# Peripherals.net
KiCad netlist of a schematic drawn in Altium Designer
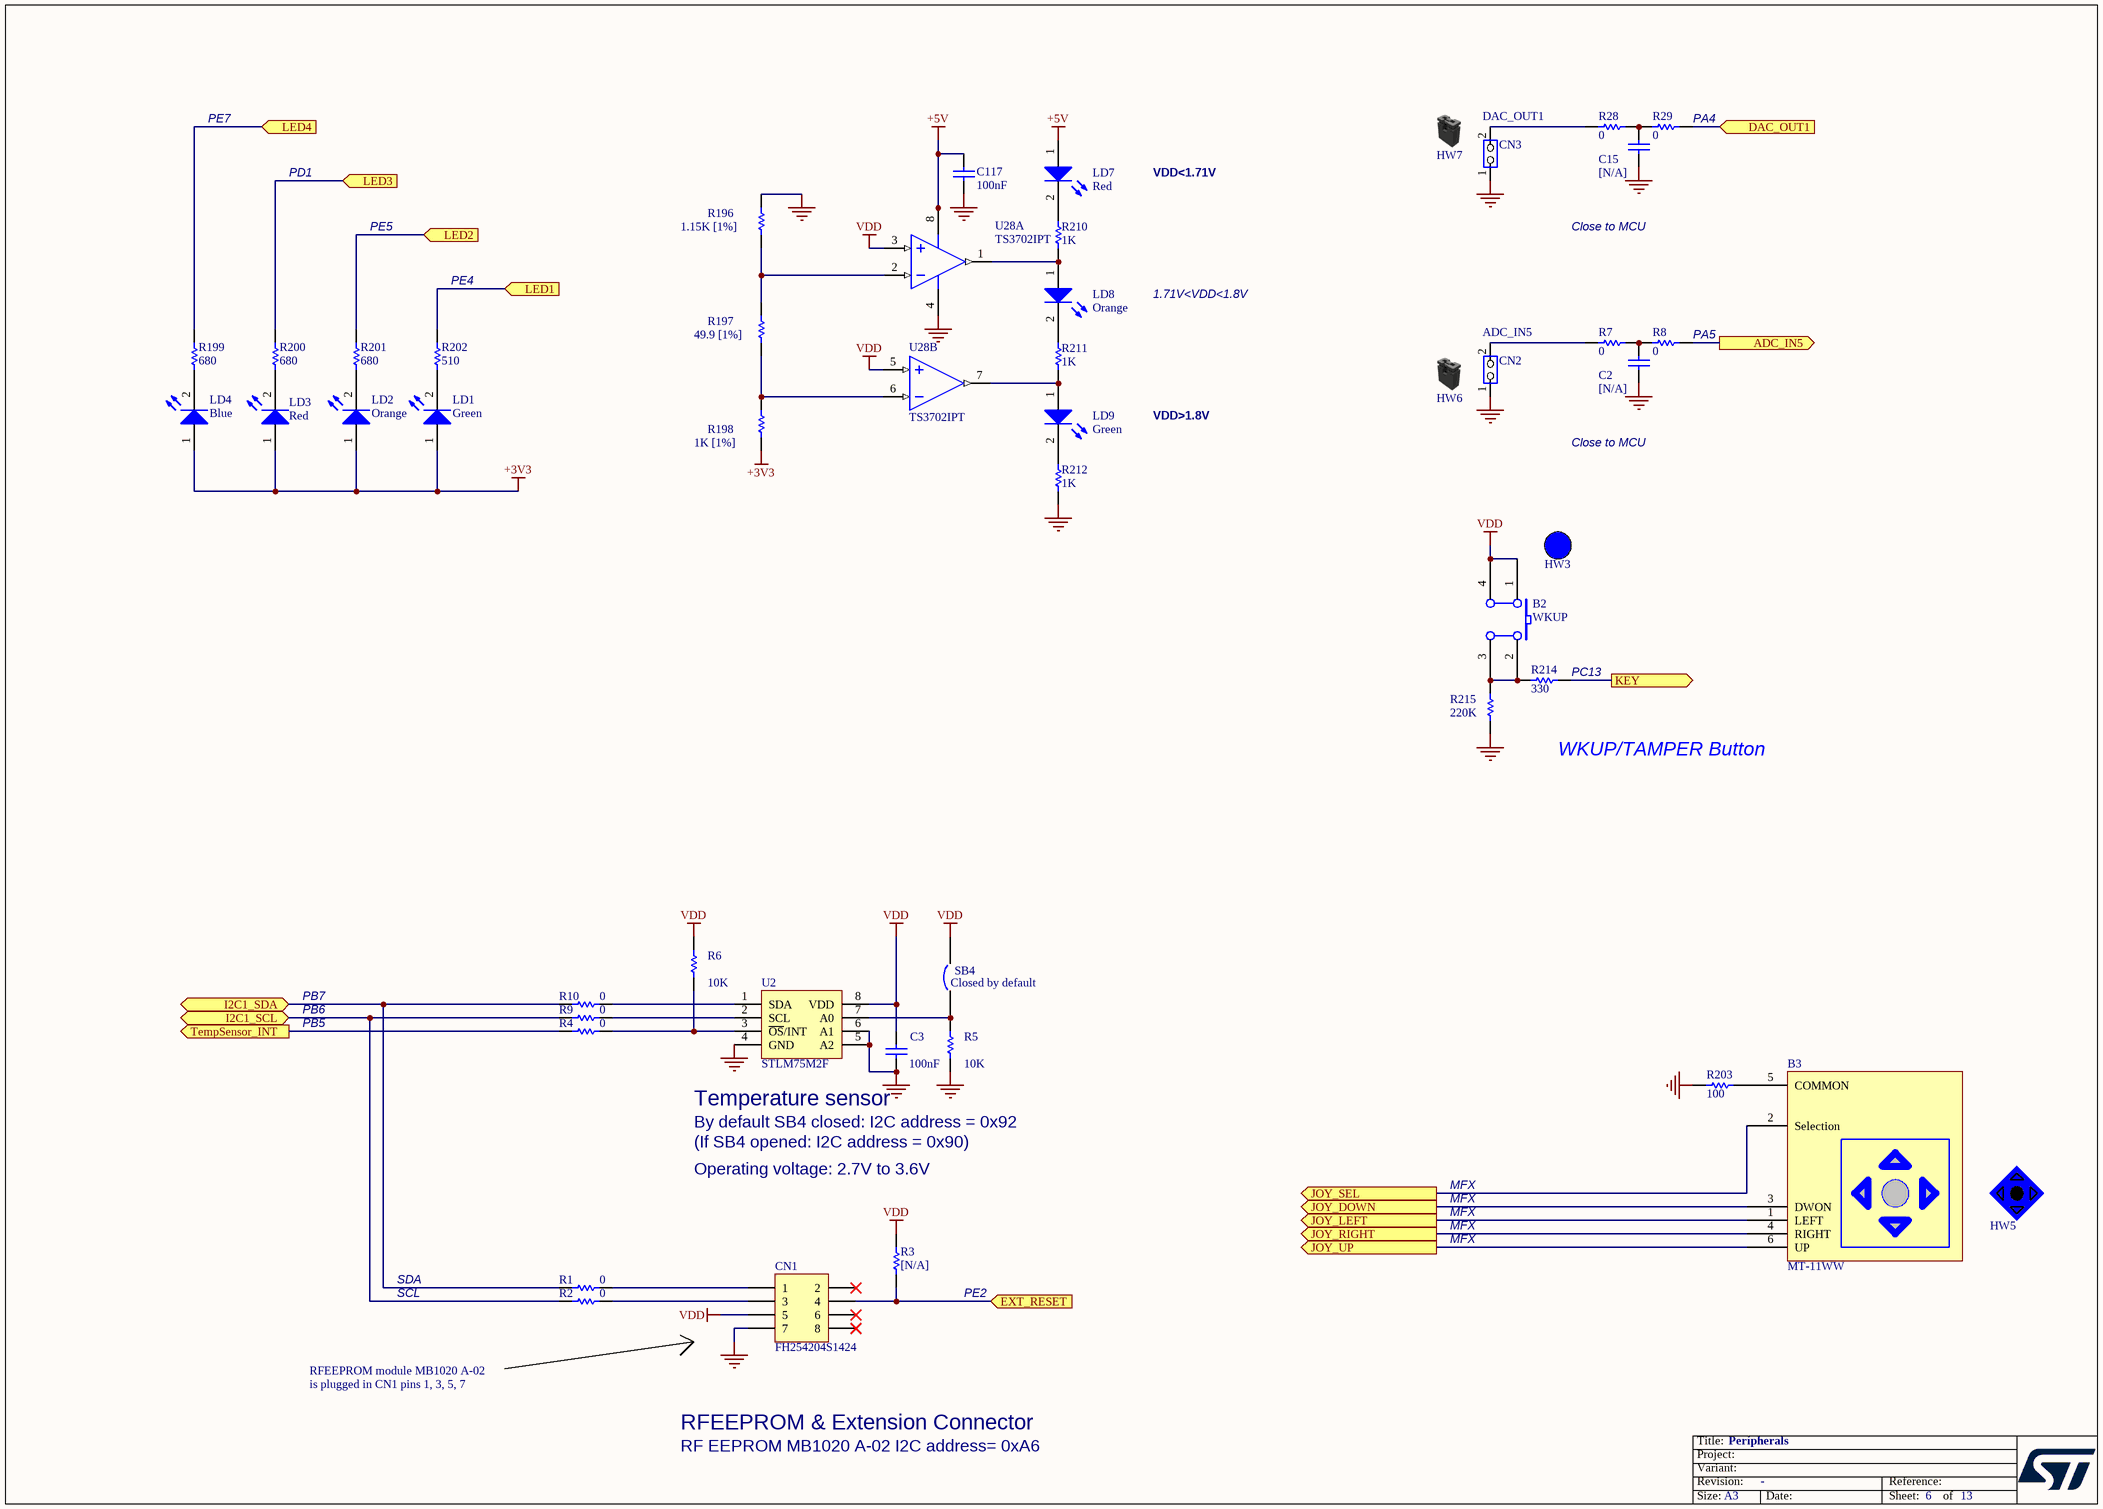
[diagram p0: Peripherals.SchDoc]

(export (version "E")
  (design (tool "Eeschema 10.0.6"))
  (components
    (comp (ref "B2")
      (value "WKUP")
      (footprint "PB10")
      (description "SE PUSHBUTTON")
      (libsource (lib "Documents") (part "SW PUSHBUTTON"))
    )
    (comp (ref "B3")
      (value "MT-11WW")
      (footprint "MT-008A")
      (description "Joystick")
      (libsource (lib "MB513") (part "MT-008A"))
    )
    (comp (ref "C2")
      (value "[N/A]")
      (footprint "0603C")
      (description "Capacitor")
      (fields (field (name "PUBLISHER") "Altium Limited"))
      (libsource (lib "Miscellaneous Devices") (part "cap"))
    )
    (comp (ref "C3")
      (value "100nF")
      (footprint "0402C")
      (description "Capacitor")
      (fields (field (name "PUBLISHER") "Altium Limited"))
      (libsource (lib "Miscellaneous Devices") (part "cap"))
    )
    (comp (ref "C15")
      (value "[N/A]")
      (footprint "0603C")
      (description "Capacitor")
      (fields (field (name "PUBLISHER") "Altium Limited"))
      (libsource (lib "Miscellaneous Devices") (part "cap"))
    )
    (comp (ref "C117")
      (value "100nF")
      (footprint "0402C")
      (description "Capacitor")
      (fields (field (name "PUBLISHER") "Altium Limited"))
      (libsource (lib "Miscellaneous Devices") (part "CAP"))
    )
    (comp (ref "CN1")
      (value "FH254204S1424")
      (footprint "SSM-104-L-DH")
      (description "Header, 5-Pin, Dual row")
      (fields (field (name "PUBLISHER") "Altium Limited"))
      (libsource (lib "mb1045") (part "SSM-104-L-DH"))
    )
    (comp (ref "CN2")
      (value "Header 2X1")
      (footprint "SIP2")
      (fields (field (name "SILKSCREEN") "ADC_IN5"))
      (libsource (lib "*") (part "JP2"))
    )
    (comp (ref "CN3")
      (value "Header 2X1")
      (footprint "SIP2")
      (fields (field (name "SILKSCREEN") "DAC_OUT1"))
      (libsource (lib "*") (part "JP2"))
    )
    (comp (ref "HW3") (value "BUTTON_HAT_BLUE") (libsource (lib "MB1168") (part "BUTTON_HAT_BLUE")))
    (comp (ref "HW5") (value "JOYSTICK_BLUE_HAT") (libsource (lib "MB1168") (part "JOYSTICK_BLUE_HAT")))
    (comp (ref "HW6") (value "Shunt Black 2.54mm") (libsource (lib "MB1168") (part "Shunt Black 2.54mm")))
    (comp (ref "HW7") (value "Shunt Black 2.54mm") (libsource (lib "MB1168") (part "Shunt Black 2.54mm")))
    (comp (ref "LD1")
      (value "Green")
      (footprint "0603D")
      (description "Typical RED, GREEN, YELLOW, AMBER GaAs LED")
      (fields (field (name "PUBLISHER") "Altium Limited"))
      (libsource (lib "Miscellaneous Devices") (part "LED2"))
    )
    (comp (ref "LD2")
      (value "Orange")
      (footprint "0603D")
      (description "Typical RED, GREEN, YELLOW, AMBER GaAs LED")
      (fields (field (name "PUBLISHER") "Altium Limited"))
      (libsource (lib "Miscellaneous Devices") (part "LED2"))
    )
    (comp (ref "LD3")
      (value "Red")
      (footprint "0603D")
      (description "Typical RED, GREEN, YELLOW, AMBER GaAs LED")
      (fields (field (name "PUBLISHER") "Altium Limited"))
      (libsource (lib "Miscellaneous Devices") (part "LED2"))
    )
    (comp (ref "LD4")
      (value "Blue")
      (footprint "0603D")
      (description "Typical RED, GREEN, YELLOW, AMBER GaAs LED")
      (fields (field (name "PUBLISHER") "Altium Limited"))
      (libsource (lib "Miscellaneous Devices") (part "LED2"))
    )
    (comp (ref "LD7")
      (value "Red")
      (footprint "0603D")
      (description "Typical RED, GREEN, YELLOW, AMBER GaAs LED")
      (fields (field (name "PUBLISHER") "Altium Limited"))
      (libsource (lib "Miscellaneous Devices") (part "LED2"))
    )
    (comp (ref "LD8")
      (value "Orange")
      (footprint "0603D")
      (description "Typical RED, GREEN, YELLOW, AMBER GaAs LED")
      (fields (field (name "PUBLISHER") "Altium Limited"))
      (libsource (lib "Miscellaneous Devices") (part "LED2"))
    )
    (comp (ref "LD9")
      (value "Green")
      (footprint "0603D")
      (description "Typical RED, GREEN, YELLOW, AMBER GaAs LED")
      (fields (field (name "PUBLISHER") "Altium Limited"))
      (libsource (lib "Miscellaneous Devices") (part "LED2"))
    )
    (comp (ref "R1")
      (value "0")
      (footprint "0603R")
      (description "Resistor")
      (fields (field (name "PUBLISHER") "Altium Limited"))
      (libsource (lib "Miscellaneous Devices") (part "Res1"))
    )
    (comp (ref "R2")
      (value "0")
      (footprint "0603R")
      (description "Resistor")
      (fields (field (name "PUBLISHER") "Altium Limited"))
      (libsource (lib "Miscellaneous Devices") (part "Res1"))
    )
    (comp (ref "R3")
      (value "[N/A]")
      (footprint "0603R")
      (description "Resistor")
      (fields (field (name "PUBLISHER") "Altium Limited"))
      (libsource (lib "Miscellaneous Devices") (part "Res1"))
    )
    (comp (ref "R4")
      (value "0")
      (footprint "0603R")
      (description "Resistor")
      (fields (field (name "PUBLISHER") "Altium Limited"))
      (libsource (lib "Miscellaneous Devices") (part "Res1"))
    )
    (comp (ref "R5")
      (value "10K")
      (footprint "0402R")
      (description "Resistor")
      (fields (field (name "PUBLISHER") "Altium Limited"))
      (libsource (lib "Miscellaneous Devices") (part "res1"))
    )
    (comp (ref "R6")
      (value "10K")
      (footprint "0402R")
      (description "Resistor")
      (fields (field (name "PUBLISHER") "Altium Limited"))
      (libsource (lib "Miscellaneous Devices") (part "res1"))
    )
    (comp (ref "R7")
      (value "0")
      (footprint "0603R")
      (description "Resistor")
      (fields (field (name "PUBLISHER") "Altium Limited"))
      (libsource (lib "Miscellaneous Devices") (part "Res1"))
    )
    (comp (ref "R8")
      (value "0")
      (footprint "0603R")
      (description "Resistor")
      (fields (field (name "PUBLISHER") "Altium Limited"))
      (libsource (lib "Miscellaneous Devices") (part "Res1"))
    )
    (comp (ref "R9")
      (value "0")
      (footprint "0603R")
      (description "Resistor")
      (fields (field (name "PUBLISHER") "Altium Limited"))
      (libsource (lib "Miscellaneous Devices") (part "Res1"))
    )
    (comp (ref "R10")
      (value "0")
      (footprint "0603R")
      (description "Resistor")
      (fields (field (name "PUBLISHER") "Altium Limited"))
      (libsource (lib "Miscellaneous Devices") (part "Res1"))
    )
    (comp (ref "R28")
      (value "0")
      (footprint "0603R")
      (description "Resistor")
      (fields (field (name "PUBLISHER") "Altium Limited"))
      (libsource (lib "Miscellaneous Devices") (part "Res1"))
    )
    (comp (ref "R29")
      (value "0")
      (footprint "0603R")
      (description "Resistor")
      (fields (field (name "PUBLISHER") "Altium Limited"))
      (libsource (lib "Miscellaneous Devices") (part "Res1"))
    )
    (comp (ref "R196")
      (value "1.15K [1%]")
      (footprint "0603R")
      (description "Resistor")
      (fields (field (name "PUBLISHER") "Altium Limited"))
      (libsource (lib "Miscellaneous Devices") (part "Res1"))
    )
    (comp (ref "R197")
      (value "49.9 [1%]")
      (footprint "0603R")
      (description "Resistor")
      (fields (field (name "PUBLISHER") "Altium Limited"))
      (libsource (lib "Miscellaneous Devices") (part "Res1"))
    )
    (comp (ref "R198")
      (value "1K [1%]")
      (footprint "0603R")
      (description "Resistor")
      (fields (field (name "PUBLISHER") "Altium Limited"))
      (libsource (lib "Miscellaneous Devices") (part "Res1"))
    )
    (comp (ref "R199")
      (value "680")
      (footprint "0402R")
      (description "Resistor")
      (fields (field (name "PUBLISHER") "Altium Limited"))
      (libsource (lib "Miscellaneous Devices") (part "Res1"))
    )
    (comp (ref "R200")
      (value "680")
      (footprint "0402R")
      (description "Resistor")
      (fields (field (name "PUBLISHER") "Altium Limited"))
      (libsource (lib "Miscellaneous Devices") (part "Res1"))
    )
    (comp (ref "R201")
      (value "680")
      (footprint "0402R")
      (description "Resistor")
      (fields (field (name "PUBLISHER") "Altium Limited"))
      (libsource (lib "Miscellaneous Devices") (part "Res1"))
    )
    (comp (ref "R202")
      (value "510")
      (footprint "0402R")
      (description "Resistor")
      (fields (field (name "PUBLISHER") "Altium Limited"))
      (libsource (lib "Miscellaneous Devices") (part "Res1"))
    )
    (comp (ref "R203")
      (value "100")
      (footprint "0402R")
      (description "Resistor")
      (fields (field (name "PUBLISHER") "Altium Limited"))
      (libsource (lib "Miscellaneous Devices") (part "Res1"))
    )
    (comp (ref "R210")
      (value "1K")
      (footprint "0402R")
      (description "Resistor")
      (fields (field (name "PUBLISHER") "Altium Limited"))
      (libsource (lib "Miscellaneous Devices") (part "Res1"))
    )
    (comp (ref "R211")
      (value "1K")
      (footprint "0402R")
      (description "Resistor")
      (fields (field (name "PUBLISHER") "Altium Limited"))
      (libsource (lib "Miscellaneous Devices") (part "Res1"))
    )
    (comp (ref "R212")
      (value "1K")
      (footprint "0402R")
      (description "Resistor")
      (fields (field (name "PUBLISHER") "Altium Limited"))
      (libsource (lib "Miscellaneous Devices") (part "Res1"))
    )
    (comp (ref "R214")
      (value "330")
      (footprint "0603R")
      (description "Resistor")
      (fields (field (name "PUBLISHER") "Altium Limited"))
      (libsource (lib "Miscellaneous Devices") (part "Res1"))
    )
    (comp (ref "R215")
      (value "220K")
      (footprint "0402R")
      (description "Resistor")
      (fields (field (name "PUBLISHER") "Altium Limited"))
      (libsource (lib "Miscellaneous Devices") (part "res1"))
    )
    (comp (ref "SB4")
      (value "Closed by default")
      (footprint "SB_0603")
      (description "Circuit Breaker")
      (fields (field (name "PUBLISHER") "Altium Limited"))
      (libsource (lib "Miscellaneous Devices") (part "Circuit Breaker"))
    )
    (comp (ref "U2")
      (value "STLM75M2F")
      (footprint "SOIC8_1R27_4R9X6")
      (libsource (lib "MB525") (part "STLM75DW2F"))
    )
    (comp (ref "U28")
      (value "TS3702IPT")
      (footprint "TSSOP8_0R65_3X6R4")
      (libsource (lib "MB819") (part "LM393PT"))
    )
  )
  (nets
    (net (code "1") (name "+3V3") (class "Default")
      (node (ref "LD1") (pin "1") (pinfunction "A_1") (pintype "passive"))
      (node (ref "LD2") (pin "1") (pinfunction "A_1") (pintype "passive"))
      (node (ref "LD3") (pin "1") (pinfunction "A_1") (pintype "passive"))
      (node (ref "LD4") (pin "1") (pinfunction "A_1") (pintype "passive"))
      (node (ref "R198") (pin "1") (pinfunction "1_1") (pintype "passive"))
    )
    (net (code "2") (name "+5V") (class "Default")
      (node (ref "C117") (pin "2") (pinfunction "2_2") (pintype "passive"))
      (node (ref "LD7") (pin "1") (pinfunction "A_1") (pintype "passive"))
      (node (ref "U28") (pin "8") (pinfunction "V+_8") (pintype "power_in"))
    )
    (net (code "3") (name "/ADC_IN5") (class "Default")
      (node (ref "R8") (pin "2") (pinfunction "2_2") (pintype "passive"))
    )
    (net (code "4") (name "/DAC_OUT1") (class "Default")
      (node (ref "R29") (pin "2") (pinfunction "2_2") (pintype "passive"))
    )
    (net (code "5") (name "/EXT_RESET") (class "Default")
      (node (ref "CN1") (pin "4") (pinfunction "4_4") (pintype "passive"))
      (node (ref "R3") (pin "1") (pinfunction "1_1") (pintype "passive"))
    )
    (net (code "6") (name "/I2C1_SCL") (class "Default")
      (node (ref "R2") (pin "1") (pinfunction "1_1") (pintype "passive"))
      (node (ref "R9") (pin "1") (pinfunction "1_1") (pintype "passive"))
    )
    (net (code "7") (name "/I2C1_SDA") (class "Default")
      (node (ref "R1") (pin "1") (pinfunction "1_1") (pintype "passive"))
      (node (ref "R10") (pin "1") (pinfunction "1_1") (pintype "passive"))
    )
    (net (code "8") (name "/JOY_DOWN") (class "Default")
      (node (ref "B3") (pin "3") (pinfunction "DWON_3") (pintype "passive"))
    )
    (net (code "9") (name "/JOY_LEFT") (class "Default")
      (node (ref "B3") (pin "1") (pinfunction "LEFT_1") (pintype "passive"))
    )
    (net (code "10") (name "/JOY_RIGHT") (class "Default")
      (node (ref "B3") (pin "4") (pinfunction "RIGHT_4") (pintype "passive"))
    )
    (net (code "11") (name "/JOY_SEL") (class "Default")
      (node (ref "B3") (pin "2") (pinfunction "Selection_2") (pintype "passive"))
    )
    (net (code "12") (name "/JOY_UP") (class "Default")
      (node (ref "B3") (pin "6") (pinfunction "UP_6") (pintype "passive"))
    )
    (net (code "13") (name "/KEY") (class "Default")
      (node (ref "R214") (pin "2") (pinfunction "2_2") (pintype "passive"))
    )
    (net (code "14") (name "/LED1") (class "Default")
      (node (ref "R202") (pin "1") (pinfunction "1_1") (pintype "passive"))
    )
    (net (code "15") (name "/LED2") (class "Default")
      (node (ref "R201") (pin "1") (pinfunction "1_1") (pintype "passive"))
    )
    (net (code "16") (name "/LED3") (class "Default")
      (node (ref "R200") (pin "1") (pinfunction "1_1") (pintype "passive"))
    )
    (net (code "17") (name "/LED4") (class "Default")
      (node (ref "R199") (pin "1") (pinfunction "1_1") (pintype "passive"))
    )
    (net (code "18") (name "/TempSensor_INT") (class "Default")
      (node (ref "R4") (pin "2") (pinfunction "2_2") (pintype "passive"))
    )
    (net (code "19") (name "GND") (class "Default")
      (node (ref "C117") (pin "1") (pinfunction "1_1") (pintype "passive"))
      (node (ref "C15") (pin "1") (pinfunction "1_1") (pintype "passive"))
      (node (ref "C2") (pin "1") (pinfunction "1_1") (pintype "passive"))
      (node (ref "C3") (pin "1") (pinfunction "1_1") (pintype "passive"))
      (node (ref "CN1") (pin "7") (pinfunction "7_7") (pintype "passive"))
      (node (ref "CN2") (pin "1") (pinfunction "COMMON_1") (pintype "passive"))
      (node (ref "CN3") (pin "1") (pinfunction "COMMON_1") (pintype "passive"))
      (node (ref "R196") (pin "2") (pinfunction "2_2") (pintype "passive"))
      (node (ref "R203") (pin "1") (pinfunction "1_1") (pintype "passive"))
      (node (ref "R212") (pin "2") (pinfunction "2_2") (pintype "passive"))
      (node (ref "R215") (pin "2") (pinfunction "2_2") (pintype "passive"))
      (node (ref "R5") (pin "2") (pinfunction "2_2") (pintype "passive"))
      (node (ref "U2") (pin "4") (pinfunction "GND_4") (pintype "passive"))
      (node (ref "U2") (pin "5") (pinfunction "A2_5") (pintype "passive"))
      (node (ref "U2") (pin "6") (pinfunction "A1_6") (pintype "passive"))
      (node (ref "U28") (pin "4") (pinfunction "V-_4") (pintype "power_in"))
    )
    (net (code "20") (name "Net-(B2-B0)") (class "Default")
      (node (ref "B2") (pin "2") (pinfunction "B0_2") (pintype "passive"))
      (node (ref "B2") (pin "3") (pinfunction "B1_3") (pintype "passive"))
      (node (ref "R214") (pin "1") (pinfunction "1_1") (pintype "passive"))
      (node (ref "R215") (pin "1") (pinfunction "1_1") (pintype "passive"))
    )
    (net (code "21") (name "Net-(B3-COMMON)") (class "Default")
      (node (ref "B3") (pin "5") (pinfunction "COMMON_5") (pintype "passive"))
      (node (ref "R203") (pin "2") (pinfunction "2_2") (pintype "passive"))
    )
    (net (code "22") (name "Net-(C2-Pad2)") (class "Default")
      (node (ref "C2") (pin "2") (pinfunction "2_2") (pintype "passive"))
      (node (ref "R7") (pin "2") (pinfunction "2_2") (pintype "passive"))
      (node (ref "R8") (pin "1") (pinfunction "1_1") (pintype "passive"))
    )
    (net (code "23") (name "Net-(C15-Pad2)") (class "Default")
      (node (ref "C15") (pin "2") (pinfunction "2_2") (pintype "passive"))
      (node (ref "R28") (pin "2") (pinfunction "2_2") (pintype "passive"))
      (node (ref "R29") (pin "1") (pinfunction "1_1") (pintype "passive"))
    )
    (net (code "24") (name "Net-(CN1-Pad1)") (class "Default")
      (node (ref "CN1") (pin "1") (pinfunction "1_1") (pintype "passive"))
      (node (ref "R1") (pin "2") (pinfunction "2_2") (pintype "passive"))
    )
    (net (code "25") (name "Net-(CN1-Pad3)") (class "Default")
      (node (ref "CN1") (pin "3") (pinfunction "3_3") (pintype "passive"))
      (node (ref "R2") (pin "2") (pinfunction "2_2") (pintype "passive"))
    )
    (net (code "26") (name "Net-(CN2-NO)") (class "Default")
      (node (ref "CN2") (pin "2") (pinfunction "NO_2") (pintype "passive"))
      (node (ref "R7") (pin "1") (pinfunction "1_1") (pintype "passive"))
    )
    (net (code "27") (name "Net-(CN3-NO)") (class "Default")
      (node (ref "CN3") (pin "2") (pinfunction "NO_2") (pintype "passive"))
      (node (ref "R28") (pin "1") (pinfunction "1_1") (pintype "passive"))
    )
    (net (code "28") (name "Net-(LD1-K)") (class "Default")
      (node (ref "LD1") (pin "2") (pinfunction "K_2") (pintype "passive"))
      (node (ref "R202") (pin "2") (pinfunction "2_2") (pintype "passive"))
    )
    (net (code "29") (name "Net-(LD2-K)") (class "Default")
      (node (ref "LD2") (pin "2") (pinfunction "K_2") (pintype "passive"))
      (node (ref "R201") (pin "2") (pinfunction "2_2") (pintype "passive"))
    )
    (net (code "30") (name "Net-(LD3-K)") (class "Default")
      (node (ref "LD3") (pin "2") (pinfunction "K_2") (pintype "passive"))
      (node (ref "R200") (pin "2") (pinfunction "2_2") (pintype "passive"))
    )
    (net (code "31") (name "Net-(LD4-K)") (class "Default")
      (node (ref "LD4") (pin "2") (pinfunction "K_2") (pintype "passive"))
      (node (ref "R199") (pin "2") (pinfunction "2_2") (pintype "passive"))
    )
    (net (code "32") (name "Net-(LD7-K)") (class "Default")
      (node (ref "LD7") (pin "2") (pinfunction "K_2") (pintype "passive"))
      (node (ref "R210") (pin "1") (pinfunction "1_1") (pintype "passive"))
    )
    (net (code "33") (name "Net-(LD8-A)") (class "Default")
      (node (ref "LD8") (pin "1") (pinfunction "A_1") (pintype "passive"))
      (node (ref "R210") (pin "2") (pinfunction "2_2") (pintype "passive"))
      (node (ref "U28") (pin "1") (pinfunction "OUT_1") (pintype "output"))
    )
    (net (code "34") (name "Net-(LD8-K)") (class "Default")
      (node (ref "LD8") (pin "2") (pinfunction "K_2") (pintype "passive"))
      (node (ref "R211") (pin "1") (pinfunction "1_1") (pintype "passive"))
    )
    (net (code "35") (name "Net-(LD9-A)") (class "Default")
      (node (ref "LD9") (pin "1") (pinfunction "A_1") (pintype "passive"))
      (node (ref "R211") (pin "2") (pinfunction "2_2") (pintype "passive"))
      (node (ref "U28") (pin "7") (pinfunction "OUT_7") (pintype "output"))
    )
    (net (code "36") (name "Net-(LD9-K)") (class "Default")
      (node (ref "LD9") (pin "2") (pinfunction "K_2") (pintype "passive"))
      (node (ref "R212") (pin "1") (pinfunction "1_1") (pintype "passive"))
    )
    (net (code "37") (name "Net-(U2-A0)") (class "Default")
      (node (ref "R5") (pin "1") (pinfunction "1_1") (pintype "passive"))
      (node (ref "SB4") (pin "1") (pinfunction "1_1") (pintype "passive"))
      (node (ref "U2") (pin "7") (pinfunction "A0_7") (pintype "passive"))
    )
    (net (code "38") (name "Net-(U2-SCL)") (class "Default")
      (node (ref "R9") (pin "2") (pinfunction "2_2") (pintype "passive"))
      (node (ref "U2") (pin "2") (pinfunction "SCL_2") (pintype "passive"))
    )
    (net (code "39") (name "Net-(U2-SDA)") (class "Default")
      (node (ref "R10") (pin "2") (pinfunction "2_2") (pintype "passive"))
      (node (ref "U2") (pin "1") (pinfunction "SDA_1") (pintype "passive"))
    )
    (net (code "40") (name "Net-(U2-~{OS}{slash}INT)") (class "Default")
      (node (ref "R4") (pin "1") (pinfunction "1_1") (pintype "passive"))
      (node (ref "R6") (pin "2") (pinfunction "2_2") (pintype "passive"))
      (node (ref "U2") (pin "3") (pinfunction "~{OS}/INT_3") (pintype "passive"))
    )
    (net (code "41") (name "Net-(U28A-IN-)") (class "Default")
      (node (ref "R196") (pin "1") (pinfunction "1_1") (pintype "passive"))
      (node (ref "R197") (pin "2") (pinfunction "2_2") (pintype "passive"))
      (node (ref "U28") (pin "2") (pinfunction "IN-_2") (pintype "input"))
    )
    (net (code "42") (name "Net-(U28B-IN-)") (class "Default")
      (node (ref "R197") (pin "1") (pinfunction "1_1") (pintype "passive"))
      (node (ref "R198") (pin "2") (pinfunction "2_2") (pintype "passive"))
      (node (ref "U28") (pin "6") (pinfunction "IN-_6") (pintype "input"))
    )
    (net (code "43") (name "VDD") (class "Default")
      (node (ref "B2") (pin "1") (pinfunction "A0_1") (pintype "passive"))
      (node (ref "B2") (pin "4") (pinfunction "A1_4") (pintype "passive"))
      (node (ref "C3") (pin "2") (pinfunction "2_2") (pintype "passive"))
      (node (ref "CN1") (pin "5") (pinfunction "5_5") (pintype "passive"))
      (node (ref "R3") (pin "2") (pinfunction "2_2") (pintype "passive"))
      (node (ref "R6") (pin "1") (pinfunction "1_1") (pintype "passive"))
      (node (ref "SB4") (pin "2") (pinfunction "2_2") (pintype "passive"))
      (node (ref "U2") (pin "8") (pinfunction "VDD_8") (pintype "passive"))
      (node (ref "U28") (pin "3") (pinfunction "IN+_3") (pintype "input"))
      (node (ref "U28") (pin "5") (pinfunction "IN+_5") (pintype "input"))
    )
    (net (code "44") (name "unconnected-(CN1-Pad2)") (class "Default")
      (node (ref "CN1") (pin "2") (pinfunction "2_2") (pintype "passive+no_connect"))
    )
    (net (code "45") (name "unconnected-(CN1-Pad6)") (class "Default")
      (node (ref "CN1") (pin "6") (pinfunction "6_6") (pintype "passive+no_connect"))
    )
    (net (code "46") (name "unconnected-(CN1-Pad8)") (class "Default")
      (node (ref "CN1") (pin "8") (pinfunction "8_8") (pintype "passive+no_connect"))
    )
  )
)
